# RingTop.net
KiCad netlist of a schematic drawn in EAGLE
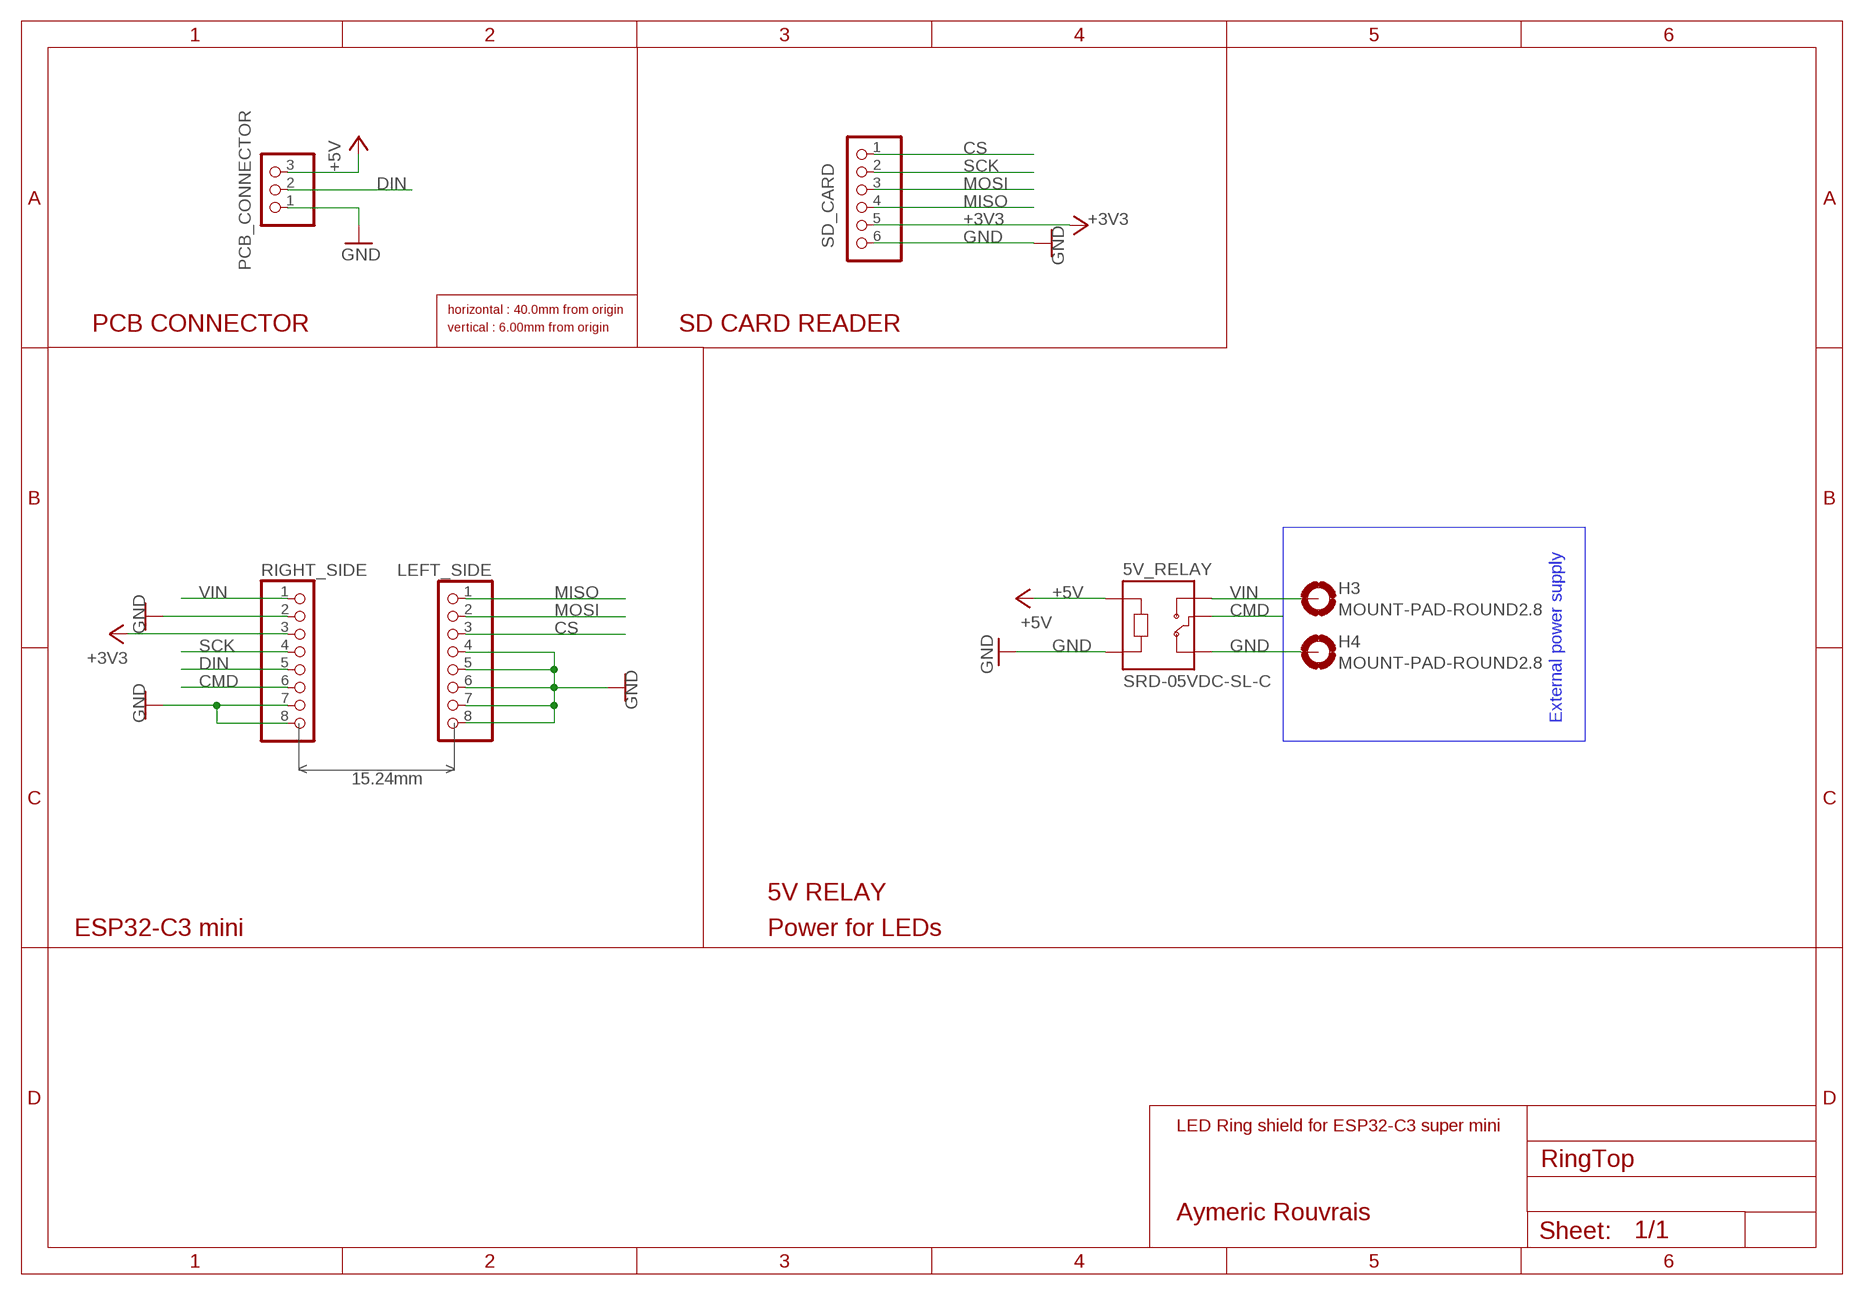
[diagram p0: schematic, sheet 1]

(export (version "E")
  (design (tool "Eeschema 10.0.6"))
  (components
    (comp (ref "5V_RELAY")
      (value "SRD-05VDC-SL-C")
      (footprint "eagle-import:RELAY_SRD-05VDC-SL-C")
      (fields (field (name "MF") "Songle Relay"))
      (libsource (lib "eagle-import") (part "SRD-05VDC-SL-C"))
    )
    (comp (ref "H3")
      (value "MOUNT-PAD-ROUND2.8")
      (footprint "eagle-import:2,8-PAD")
      (libsource (lib "eagle-import") (part "MOUNT-PAD-ROUND2.8"))
    )
    (comp (ref "H4")
      (value "MOUNT-PAD-ROUND2.8")
      (footprint "eagle-import:2,8-PAD")
      (libsource (lib "eagle-import") (part "MOUNT-PAD-ROUND2.8"))
    )
    (comp (ref "LEFT_SIDE")
      (value "PINHD-1X8")
      (footprint "eagle-import:1X08")
      (libsource (lib "eagle-import") (part "PINHD-1X8"))
    )
    (comp (ref "PCB_CONNECTOR")
      (value "PINHD-1X3")
      (footprint "eagle-import:1X03")
      (libsource (lib "eagle-import") (part "PINHD-1X3"))
    )
    (comp (ref "RIGHT_SIDE")
      (value "PINHD-1X8")
      (footprint "eagle-import:1X08")
      (libsource (lib "eagle-import") (part "PINHD-1X8"))
    )
    (comp (ref "SD_CARD")
      (value "PINHD-1X6/90")
      (footprint "eagle-import:1X06_90")
      (libsource (lib "eagle-import") (part "PINHD-1X6/90"))
    )
  )
  (nets
    (net (code "1") (name "+3V3") (class "Default")
      (node (ref "RIGHT_SIDE") (pin "3") (pinfunction "3_3") (pintype "passive"))
      (node (ref "SD_CARD") (pin "5") (pinfunction "5_5") (pintype "passive"))
    )
    (net (code "2") (name "+5V") (class "Default")
      (node (ref "5V_RELAY") (pin "A1") (pinfunction "A1_A1") (pintype "passive"))
      (node (ref "PCB_CONNECTOR") (pin "3") (pinfunction "3_3") (pintype "passive"))
    )
    (net (code "3") (name "/CMD") (class "Default")
      (node (ref "5V_RELAY") (pin "COM") (pinfunction "COM_COM") (pintype "passive"))
      (node (ref "RIGHT_SIDE") (pin "6") (pinfunction "6_6") (pintype "passive"))
    )
    (net (code "4") (name "/CS") (class "Default")
      (node (ref "LEFT_SIDE") (pin "3") (pinfunction "3_3") (pintype "passive"))
      (node (ref "SD_CARD") (pin "1") (pinfunction "1_1") (pintype "passive"))
    )
    (net (code "5") (name "/DIN") (class "Default")
      (node (ref "PCB_CONNECTOR") (pin "2") (pinfunction "2_2") (pintype "passive"))
      (node (ref "RIGHT_SIDE") (pin "5") (pinfunction "5_5") (pintype "passive"))
    )
    (net (code "6") (name "/MISO") (class "Default")
      (node (ref "LEFT_SIDE") (pin "1") (pinfunction "1_1") (pintype "passive"))
      (node (ref "SD_CARD") (pin "4") (pinfunction "4_4") (pintype "passive"))
    )
    (net (code "7") (name "/MOSI") (class "Default")
      (node (ref "LEFT_SIDE") (pin "2") (pinfunction "2_2") (pintype "passive"))
      (node (ref "SD_CARD") (pin "3") (pinfunction "3_3") (pintype "passive"))
    )
    (net (code "8") (name "/SCK") (class "Default")
      (node (ref "RIGHT_SIDE") (pin "4") (pinfunction "4_4") (pintype "passive"))
      (node (ref "SD_CARD") (pin "2") (pinfunction "2_2") (pintype "passive"))
    )
    (net (code "9") (name "/VIN") (class "Default")
      (node (ref "5V_RELAY") (pin "NO") (pinfunction "NO_NO") (pintype "passive"))
      (node (ref "H3") (pin "B2,8") (pinfunction "MOUNT_B2,8") (pintype "passive"))
      (node (ref "RIGHT_SIDE") (pin "1") (pinfunction "1_1") (pintype "passive"))
    )
    (net (code "10") (name "GND") (class "Default")
      (node (ref "5V_RELAY") (pin "A2") (pinfunction "A2_A2") (pintype "passive"))
      (node (ref "5V_RELAY") (pin "NC") (pinfunction "NC_NC") (pintype "passive"))
      (node (ref "H4") (pin "B2,8") (pinfunction "MOUNT_B2,8") (pintype "passive"))
      (node (ref "LEFT_SIDE") (pin "4") (pinfunction "4_4") (pintype "passive"))
      (node (ref "LEFT_SIDE") (pin "5") (pinfunction "5_5") (pintype "passive"))
      (node (ref "LEFT_SIDE") (pin "6") (pinfunction "6_6") (pintype "passive"))
      (node (ref "LEFT_SIDE") (pin "7") (pinfunction "7_7") (pintype "passive"))
      (node (ref "LEFT_SIDE") (pin "8") (pinfunction "8_8") (pintype "passive"))
      (node (ref "PCB_CONNECTOR") (pin "1") (pinfunction "1_1") (pintype "passive"))
      (node (ref "RIGHT_SIDE") (pin "2") (pinfunction "2_2") (pintype "passive"))
      (node (ref "RIGHT_SIDE") (pin "7") (pinfunction "7_7") (pintype "passive"))
      (node (ref "RIGHT_SIDE") (pin "8") (pinfunction "8_8") (pintype "passive"))
      (node (ref "SD_CARD") (pin "6") (pinfunction "6_6") (pintype "passive"))
    )
  )
)
